# EnDat-Biss.net
KiCad netlist of a schematic drawn in Altium Designer
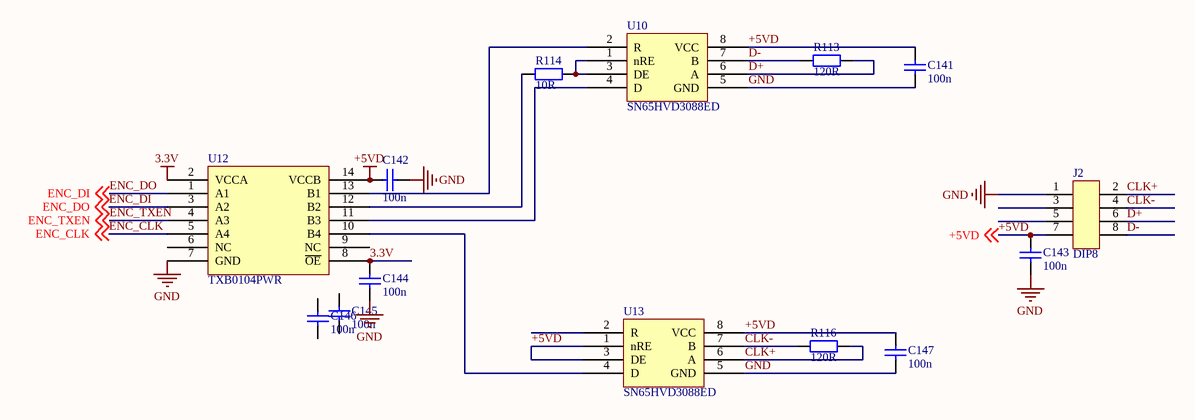
[diagram p0: EnDat-Biss.SchDoc]

(export (version "E")
  (design (tool "Eeschema 10.0.6"))
  (components
    (comp (ref "C141")
      (value "100n")
      (footprint "0603C")
      (description "Capacitor")
      (fields (field (name "PUBLISHER") "Altium Limited"))
      (libsource (lib "Main_C") (part "Cap"))
    )
    (comp (ref "C142")
      (value "100n")
      (footprint "0603C")
      (description "Capacitor")
      (fields (field (name "PUBLISHER") "Altium Limited"))
      (libsource (lib "Main_C") (part "Cap"))
    )
    (comp (ref "C143")
      (value "100n")
      (footprint "0603C")
      (description "Capacitor")
      (fields (field (name "PUBLISHER") "Altium Limited"))
      (libsource (lib "Main_C") (part "Cap"))
    )
    (comp (ref "C144")
      (value "100n")
      (footprint "0603C")
      (description "Capacitor")
      (fields (field (name "PUBLISHER") "Altium Limited"))
      (libsource (lib "Main_C") (part "Cap"))
    )
    (comp (ref "C145")
      (value "100n")
      (footprint "0603C")
      (description "Capacitor")
      (fields (field (name "PUBLISHER") "Altium Limited"))
      (libsource (lib "Main_C") (part "Cap"))
    )
    (comp (ref "C146")
      (value "100n")
      (footprint "0603C")
      (description "Capacitor")
      (fields (field (name "PUBLISHER") "Altium Limited"))
      (libsource (lib "Main_C") (part "Cap"))
    )
    (comp (ref "C147")
      (value "100n")
      (footprint "0603C")
      (description "Capacitor")
      (fields (field (name "PUBLISHER") "Altium Limited"))
      (libsource (lib "Main_C") (part "Cap"))
    )
    (comp (ref "J2")
      (value "DIP8")
      (footprint "DIP8-2.54")
      (description "Connectors")
      (fields (field (name "PUBLISHER") "Altium Limited"))
      (libsource (lib "jointbar") (part "DIP8"))
    )
    (comp (ref "R113")
      (value "120R")
      (footprint "0603R")
      (description "Resistor")
      (fields (field (name "PUBLISHER") "Altium Limited"))
      (libsource (lib "Main_C") (part "Res2"))
    )
    (comp (ref "R114")
      (value "10R")
      (footprint "0603R")
      (description "Resistor")
      (fields (field (name "PUBLISHER") "Altium Limited"))
      (libsource (lib "Main_C") (part "Res2"))
    )
    (comp (ref "R116")
      (value "120R")
      (footprint "0603R")
      (description "Resistor")
      (fields (field (name "PUBLISHER") "Altium Limited"))
      (libsource (lib "Main_C") (part "Res2"))
    )
    (comp (ref "U10")
      (value "SN65HVD3088ED")
      (footprint "SOIC-8")
      (libsource (lib "Main_C") (part "SN65HVD3088"))
    )
    (comp (ref "U12") (value "TXB0104PWR") (footprint "TSSOP-14") (libsource (lib "Main_C") (part "TXB0104")))
    (comp (ref "U13")
      (value "SN65HVD3088ED")
      (footprint "SOIC-8")
      (libsource (lib "Main_C") (part "SN65HVD3088"))
    )
  )
  (nets
    (net (code "1") (name "+5VD") (class "Default")
      (node (ref "C141") (pin "2") (pinfunction "2_2") (pintype "passive"))
      (node (ref "C142") (pin "2") (pinfunction "2_2") (pintype "passive"))
      (node (ref "C143") (pin "1") (pinfunction "1_1") (pintype "passive"))
      (node (ref "C147") (pin "2") (pinfunction "2_2") (pintype "passive"))
      (node (ref "J2") (pin "7") (pinfunction "7_7") (pintype "passive"))
      (node (ref "U10") (pin "8") (pinfunction "VCC_8") (pintype "passive"))
      (node (ref "U12") (pin "14") (pinfunction "VCCB_14") (pintype "passive"))
      (node (ref "U13") (pin "1") (pinfunction "nRE_1") (pintype "passive"))
      (node (ref "U13") (pin "3") (pinfunction "DE_3") (pintype "passive"))
      (node (ref "U13") (pin "8") (pinfunction "VCC_8") (pintype "passive"))
    )
    (net (code "2") (name "/CLK+") (class "Default")
      (node (ref "J2") (pin "2") (pinfunction "2_2") (pintype "passive"))
      (node (ref "R116") (pin "1") (pinfunction "1_1") (pintype "passive"))
      (node (ref "U13") (pin "6") (pinfunction "A_6") (pintype "passive"))
    )
    (net (code "3") (name "/CLK-") (class "Default")
      (node (ref "J2") (pin "4") (pinfunction "4_4") (pintype "passive"))
      (node (ref "R116") (pin "2") (pinfunction "2_2") (pintype "passive"))
      (node (ref "U13") (pin "7") (pinfunction "B_7") (pintype "passive"))
    )
    (net (code "4") (name "/D+") (class "Default")
      (node (ref "J2") (pin "6") (pinfunction "6_6") (pintype "passive"))
      (node (ref "R113") (pin "1") (pinfunction "1_1") (pintype "passive"))
      (node (ref "U10") (pin "6") (pinfunction "A_6") (pintype "passive"))
    )
    (net (code "5") (name "/D-") (class "Default")
      (node (ref "J2") (pin "8") (pinfunction "8_8") (pintype "passive"))
      (node (ref "R113") (pin "2") (pinfunction "2_2") (pintype "passive"))
      (node (ref "U10") (pin "7") (pinfunction "B_7") (pintype "passive"))
    )
    (net (code "6") (name "3.3V") (class "Default")
      (node (ref "C144") (pin "1") (pinfunction "1_1") (pintype "passive"))
      (node (ref "U12") (pin "2") (pinfunction "VCCA_2") (pintype "passive"))
      (node (ref "U12") (pin "8") (pinfunction "~{OE}_8") (pintype "passive"))
    )
    (net (code "7") (name "ENC_CLK") (class "Default")
      (node (ref "U12") (pin "5") (pinfunction "A4_5") (pintype "passive"))
    )
    (net (code "8") (name "ENC_DI") (class "Default")
      (node (ref "U12") (pin "1") (pinfunction "A1_1") (pintype "passive"))
      (node (ref "U12") (pin "3") (pinfunction "A2_3") (pintype "passive"))
    )
    (net (code "9") (name "ENC_TXEN") (class "Default")
      (node (ref "U12") (pin "4") (pinfunction "A3_4") (pintype "passive"))
    )
    (net (code "10") (name "GND") (class "Default")
      (node (ref "C141") (pin "1") (pinfunction "1_1") (pintype "passive"))
      (node (ref "C142") (pin "1") (pinfunction "1_1") (pintype "passive"))
      (node (ref "C143") (pin "2") (pinfunction "2_2") (pintype "passive"))
      (node (ref "C144") (pin "2") (pinfunction "2_2") (pintype "passive"))
      (node (ref "C147") (pin "1") (pinfunction "1_1") (pintype "passive"))
      (node (ref "J2") (pin "1") (pinfunction "1_1") (pintype "passive"))
      (node (ref "U10") (pin "5") (pinfunction "GND_5") (pintype "passive"))
      (node (ref "U12") (pin "7") (pinfunction "GND_7") (pintype "passive"))
      (node (ref "U13") (pin "5") (pinfunction "GND_5") (pintype "passive"))
    )
    (net (code "11") (name "Net-(U10-D)") (class "Default")
      (node (ref "U10") (pin "4") (pinfunction "D_4") (pintype "passive"))
      (node (ref "U12") (pin "11") (pinfunction "B3_11") (pintype "passive"))
    )
    (net (code "12") (name "Net-(U10-DE)") (class "Default")
      (node (ref "R114") (pin "1") (pinfunction "1_1") (pintype "passive"))
      (node (ref "U10") (pin "1") (pinfunction "nRE_1") (pintype "passive"))
      (node (ref "U10") (pin "3") (pinfunction "DE_3") (pintype "passive"))
    )
    (net (code "13") (name "Net-(U10-R)") (class "Default")
      (node (ref "U10") (pin "2") (pinfunction "R_2") (pintype "passive"))
      (node (ref "U12") (pin "13") (pinfunction "B1_13") (pintype "passive"))
    )
    (net (code "14") (name "Net-(U12-B2)") (class "Default")
      (node (ref "R114") (pin "2") (pinfunction "2_2") (pintype "passive"))
      (node (ref "U12") (pin "12") (pinfunction "B2_12") (pintype "passive"))
    )
    (net (code "15") (name "Net-(U12-B4)") (class "Default")
      (node (ref "U12") (pin "10") (pinfunction "B4_10") (pintype "passive"))
      (node (ref "U13") (pin "4") (pinfunction "D_4") (pintype "passive"))
    )
    (net (code "16") (name "unconnected-(C145-Pad1)") (class "Default")
      (node (ref "C145") (pin "1") (pinfunction "1_1") (pintype "passive"))
    )
    (net (code "17") (name "unconnected-(C145-Pad2)") (class "Default")
      (node (ref "C145") (pin "2") (pinfunction "2_2") (pintype "passive"))
    )
    (net (code "18") (name "unconnected-(C146-Pad1)") (class "Default")
      (node (ref "C146") (pin "1") (pinfunction "1_1") (pintype "passive"))
    )
    (net (code "19") (name "unconnected-(C146-Pad2)") (class "Default")
      (node (ref "C146") (pin "2") (pinfunction "2_2") (pintype "passive"))
    )
    (net (code "20") (name "unconnected-(J2-Pad3)") (class "Default")
      (node (ref "J2") (pin "3") (pinfunction "3_3") (pintype "passive"))
    )
    (net (code "21") (name "unconnected-(J2-Pad5)") (class "Default")
      (node (ref "J2") (pin "5") (pinfunction "5_5") (pintype "passive"))
    )
    (net (code "22") (name "unconnected-(U12-NC-Pad6)") (class "Default")
      (node (ref "U12") (pin "6") (pinfunction "NC_6") (pintype "passive"))
    )
    (net (code "23") (name "unconnected-(U12-NC-Pad9)") (class "Default")
      (node (ref "U12") (pin "9") (pinfunction "NC_9") (pintype "passive"))
    )
    (net (code "24") (name "unconnected-(U13-R-Pad2)") (class "Default")
      (node (ref "U13") (pin "2") (pinfunction "R_2") (pintype "passive"))
    )
  )
)
